# LlethrauControls.net
KiCad netlist of a schematic drawn in EAGLE
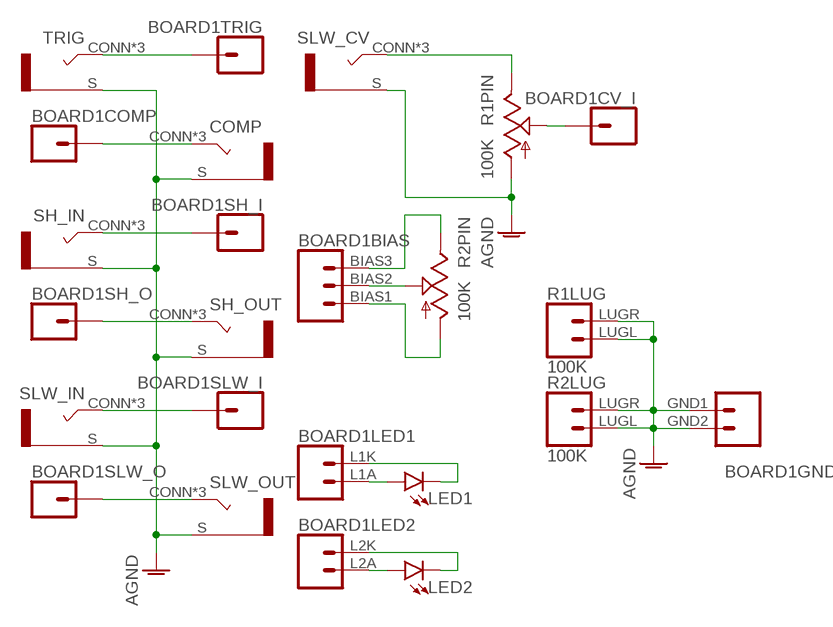
[diagram p0: schematic, sheet 1]

(export (version "E")
  (design (tool "Eeschema 10.0.6"))
  (components
    (comp (ref "BOARD1")
      (value "LLETHRAU_LINK")
      (footprint "eagle-import:LLETHRAU")
      (libsource (lib "eagle-import") (part "LLETHRAU_LINK"))
    )
    (comp (ref "COMP")
      (value "COMBI-JACKCINCHNANA")
      (footprint "eagle-import:NEWCOMBOJACK_PANEL")
      (libsource (lib "eagle-import") (part "COMBI-JACKCINCHNANA"))
    )
    (comp (ref "LED1")
      (value "LED5MM")
      (footprint "eagle-import:LED5MM")
      (libsource (lib "eagle-import") (part "LED5MM"))
    )
    (comp (ref "LED2")
      (value "LED5MM")
      (footprint "eagle-import:LED5MM")
      (libsource (lib "eagle-import") (part "LED5MM"))
    )
    (comp (ref "R1")
      (value "100K")
      (footprint "eagle-import:ALPHA_RV09_9MMPOT")
      (libsource (lib "eagle-import") (part "POTENTIOMETER"))
    )
    (comp (ref "R2")
      (value "100K")
      (footprint "eagle-import:ALPHA_RV09_9MMPOT")
      (libsource (lib "eagle-import") (part "POTENTIOMETER"))
    )
    (comp (ref "SH_IN")
      (value "COMBI-JACKCINCHNANA")
      (footprint "eagle-import:NEWCOMBOJACK_PANEL")
      (libsource (lib "eagle-import") (part "COMBI-JACKCINCHNANA"))
    )
    (comp (ref "SH_OUT")
      (value "COMBI-JACKCINCHNANA")
      (footprint "eagle-import:NEWCOMBOJACK_PANEL")
      (libsource (lib "eagle-import") (part "COMBI-JACKCINCHNANA"))
    )
    (comp (ref "SLW_CV")
      (value "COMBI-JACKCINCHNANA")
      (footprint "eagle-import:NEWCOMBOJACK_PANEL")
      (libsource (lib "eagle-import") (part "COMBI-JACKCINCHNANA"))
    )
    (comp (ref "SLW_IN")
      (value "COMBI-JACKCINCHNANA")
      (footprint "eagle-import:NEWCOMBOJACK_PANEL")
      (libsource (lib "eagle-import") (part "COMBI-JACKCINCHNANA"))
    )
    (comp (ref "SLW_OUT")
      (value "COMBI-JACKCINCHNANA")
      (footprint "eagle-import:NEWCOMBOJACK_PANEL")
      (libsource (lib "eagle-import") (part "COMBI-JACKCINCHNANA"))
    )
    (comp (ref "TRIG")
      (value "COMBI-JACKCINCHNANA")
      (footprint "eagle-import:NEWCOMBOJACK_PANEL")
      (libsource (lib "eagle-import") (part "COMBI-JACKCINCHNANA"))
    )
  )
  (nets
    (net (code "1") (name "AGND") (class "Default")
      (node (ref "BOARD1") (pin "GND1") (pinfunction "1_GND1") (pintype "passive"))
      (node (ref "BOARD1") (pin "GND2") (pinfunction "2_GND2") (pintype "passive"))
      (node (ref "COMP") (pin "S") (pinfunction "S_S") (pintype "passive"))
      (node (ref "R1") (pin "C1") (pinfunction "A_C1") (pintype "passive"))
      (node (ref "R1") (pin "LUGL") (pinfunction "1_LUGL") (pintype "passive"))
      (node (ref "R1") (pin "LUGR") (pinfunction "2_LUGR") (pintype "passive"))
      (node (ref "R2") (pin "LUGL") (pinfunction "1_LUGL") (pintype "passive"))
      (node (ref "R2") (pin "LUGR") (pinfunction "2_LUGR") (pintype "passive"))
      (node (ref "SH_IN") (pin "S") (pinfunction "S_S") (pintype "passive"))
      (node (ref "SH_OUT") (pin "S") (pinfunction "S_S") (pintype "passive"))
      (node (ref "SLW_CV") (pin "S") (pinfunction "S_S") (pintype "passive"))
      (node (ref "SLW_IN") (pin "S") (pinfunction "S_S") (pintype "passive"))
      (node (ref "SLW_OUT") (pin "S") (pinfunction "S_S") (pintype "passive"))
      (node (ref "TRIG") (pin "S") (pinfunction "S_S") (pintype "passive"))
    )
    (net (code "2") (name "Net-(BOARD1A-1)") (class "Default")
      (node (ref "BOARD1") (pin "BIAS1") (pinfunction "1_BIAS1") (pintype "passive"))
      (node (ref "R2") (pin "C1") (pinfunction "A_C1") (pintype "passive"))
    )
    (net (code "3") (name "Net-(BOARD1A-2)") (class "Default")
      (node (ref "BOARD1") (pin "BIAS2") (pinfunction "2_BIAS2") (pintype "passive"))
      (node (ref "R2") (pin "C2") (pinfunction "W_C2") (pintype "passive"))
    )
    (net (code "4") (name "Net-(BOARD1A-3)") (class "Default")
      (node (ref "BOARD1") (pin "BIAS3") (pinfunction "3_BIAS3") (pintype "passive"))
      (node (ref "R2") (pin "C3") (pinfunction "B_C3") (pintype "passive"))
    )
    (net (code "5") (name "Net-(BOARD1B-1)") (class "Default")
      (node (ref "BOARD1") (pin "COMP") (pinfunction "1_COMP") (pintype "passive"))
      (node (ref "COMP") (pin "CONN") (pinfunction "T_CONN") (pintype "passive"))
      (node (ref "COMP") (pin "T1") (pinfunction "T_T1") (pintype "passive"))
      (node (ref "COMP") (pin "T2") (pinfunction "T_T2") (pintype "passive"))
    )
    (net (code "6") (name "Net-(BOARD1C-1)") (class "Default")
      (node (ref "BOARD1") (pin "CV_I") (pinfunction "1_CV_I") (pintype "passive"))
      (node (ref "R1") (pin "C2") (pinfunction "W_C2") (pintype "passive"))
    )
    (net (code "7") (name "Net-(BOARD1E-1)") (class "Default")
      (node (ref "BOARD1") (pin "L1A") (pinfunction "1_L1A") (pintype "passive"))
      (node (ref "LED1") (pin "A") (pinfunction "A_A") (pintype "passive"))
    )
    (net (code "8") (name "Net-(BOARD1E-2)") (class "Default")
      (node (ref "BOARD1") (pin "L1K") (pinfunction "2_L1K") (pintype "passive"))
      (node (ref "LED1") (pin "K") (pinfunction "C_K") (pintype "passive"))
    )
    (net (code "9") (name "Net-(BOARD1F-1)") (class "Default")
      (node (ref "BOARD1") (pin "L2A") (pinfunction "1_L2A") (pintype "passive"))
      (node (ref "LED2") (pin "A") (pinfunction "A_A") (pintype "passive"))
    )
    (net (code "10") (name "Net-(BOARD1F-2)") (class "Default")
      (node (ref "BOARD1") (pin "L2K") (pinfunction "2_L2K") (pintype "passive"))
      (node (ref "LED2") (pin "K") (pinfunction "C_K") (pintype "passive"))
    )
    (net (code "11") (name "Net-(BOARD1G-1)") (class "Default")
      (node (ref "BOARD1") (pin "SH_I") (pinfunction "1_SH_I") (pintype "passive"))
      (node (ref "SH_IN") (pin "CONN") (pinfunction "T_CONN") (pintype "passive"))
      (node (ref "SH_IN") (pin "T1") (pinfunction "T_T1") (pintype "passive"))
      (node (ref "SH_IN") (pin "T2") (pinfunction "T_T2") (pintype "passive"))
    )
    (net (code "12") (name "Net-(BOARD1H-1)") (class "Default")
      (node (ref "BOARD1") (pin "SH_O") (pinfunction "1_SH_O") (pintype "passive"))
      (node (ref "SH_OUT") (pin "CONN") (pinfunction "T_CONN") (pintype "passive"))
      (node (ref "SH_OUT") (pin "T1") (pinfunction "T_T1") (pintype "passive"))
      (node (ref "SH_OUT") (pin "T2") (pinfunction "T_T2") (pintype "passive"))
    )
    (net (code "13") (name "Net-(BOARD1I-1)") (class "Default")
      (node (ref "BOARD1") (pin "SLW_I") (pinfunction "1_SLW_I") (pintype "passive"))
      (node (ref "SLW_IN") (pin "CONN") (pinfunction "T_CONN") (pintype "passive"))
      (node (ref "SLW_IN") (pin "T1") (pinfunction "T_T1") (pintype "passive"))
      (node (ref "SLW_IN") (pin "T2") (pinfunction "T_T2") (pintype "passive"))
    )
    (net (code "14") (name "Net-(BOARD1J-1)") (class "Default")
      (node (ref "BOARD1") (pin "SLW_O") (pinfunction "1_SLW_O") (pintype "passive"))
      (node (ref "SLW_OUT") (pin "CONN") (pinfunction "T_CONN") (pintype "passive"))
      (node (ref "SLW_OUT") (pin "T1") (pinfunction "T_T1") (pintype "passive"))
      (node (ref "SLW_OUT") (pin "T2") (pinfunction "T_T2") (pintype "passive"))
    )
    (net (code "15") (name "Net-(BOARD1K-1)") (class "Default")
      (node (ref "BOARD1") (pin "TRIG") (pinfunction "1_TRIG") (pintype "passive"))
      (node (ref "TRIG") (pin "CONN") (pinfunction "T_CONN") (pintype "passive"))
      (node (ref "TRIG") (pin "T1") (pinfunction "T_T1") (pintype "passive"))
      (node (ref "TRIG") (pin "T2") (pinfunction "T_T2") (pintype "passive"))
    )
    (net (code "16") (name "Net-(R1B-B)") (class "Default")
      (node (ref "R1") (pin "C3") (pinfunction "B_C3") (pintype "passive"))
      (node (ref "SLW_CV") (pin "CONN") (pinfunction "T_CONN") (pintype "passive"))
      (node (ref "SLW_CV") (pin "T1") (pinfunction "T_T1") (pintype "passive"))
      (node (ref "SLW_CV") (pin "T2") (pinfunction "T_T2") (pintype "passive"))
    )
  )
)
